# Comunicaciones.net
KiCad netlist of a schematic drawn in Altium Designer
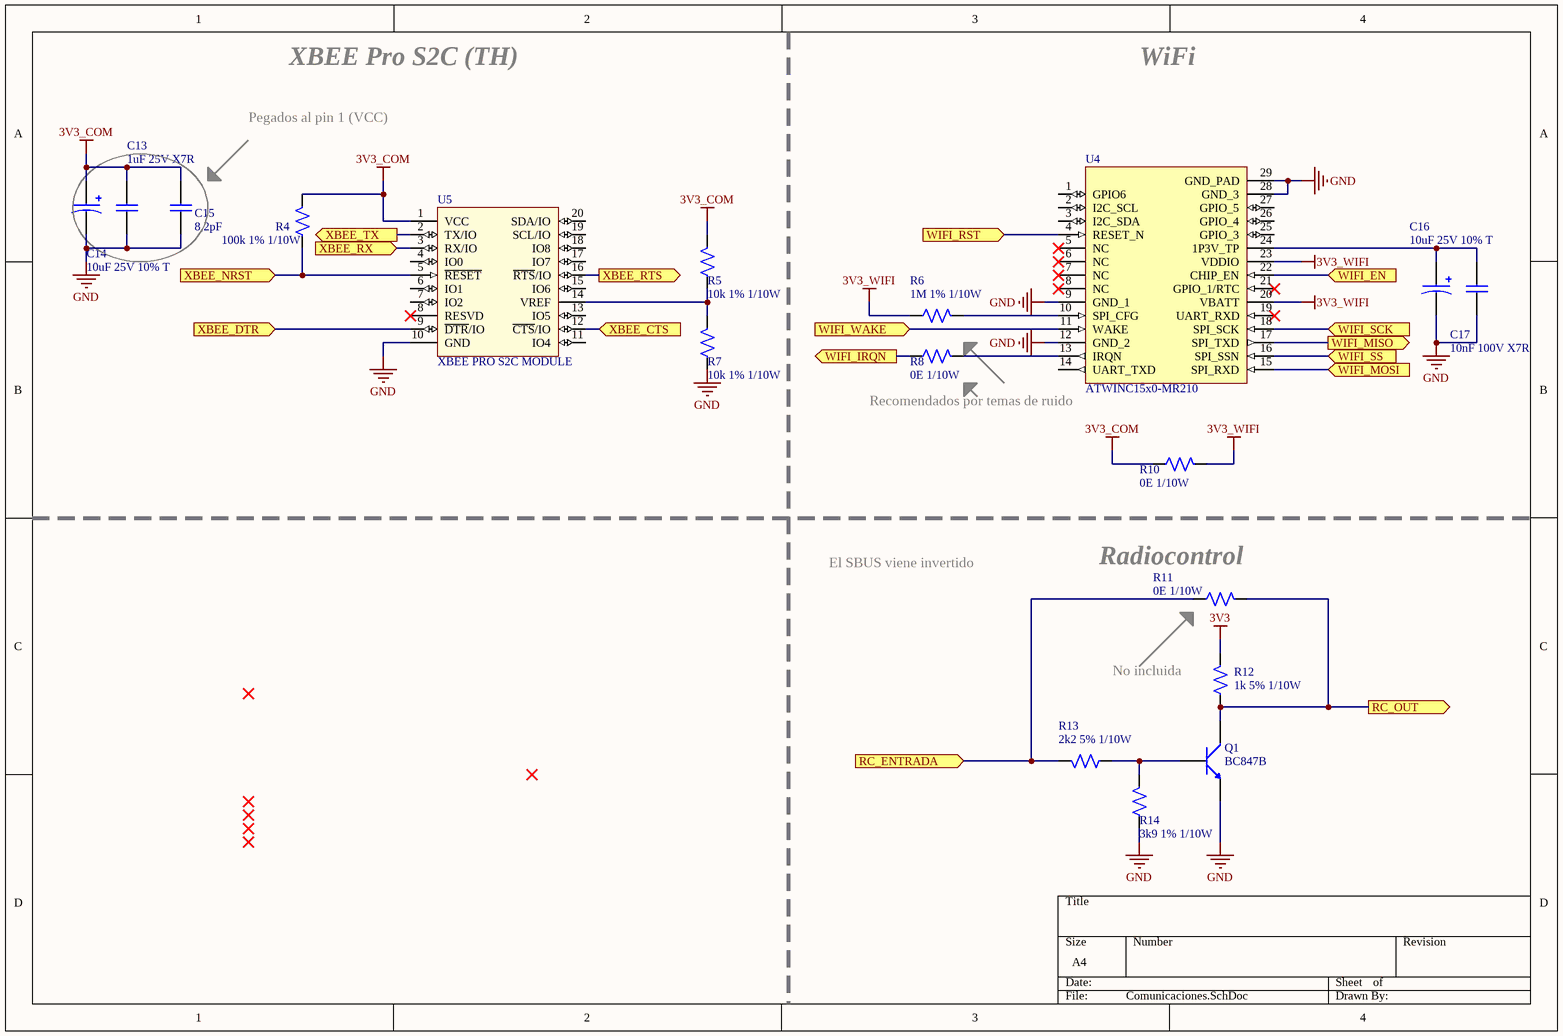
[diagram p0: Comunicaciones.SchDoc]

(export (version "E")
  (design (tool "Eeschema 10.0.6"))
  (components
    (comp (ref "C13")
      (value "1uF 25V X7R")
      (footprint "C0603")
      (description "Capacitor de placas paralelas")
      (libsource (lib "HW_Dron_V2") (part "Capacitor"))
    )
    (comp (ref "C14")
      (value "10uF 25V 10% T")
      (footprint "AVX_C")
      (description "Capacitor polarizado")
      (libsource (lib "HW_Dron_V2") (part "CapaPol"))
    )
    (comp (ref "C15")
      (value "8,2pF 50V COG 5%")
      (footprint "C0603")
      (description "Capacitor de placas paralelas")
      (fields (field (name "VALOR") "8,2pF"))
      (libsource (lib "HW_Dron_V2") (part "Capacitor"))
    )
    (comp (ref "C16")
      (value "10uF 25V 10% T")
      (footprint "AVX_C")
      (description "Capacitor polarizado")
      (libsource (lib "HW_Dron_V2") (part "CapaPol"))
    )
    (comp (ref "C17")
      (value "10nF 100V X7R")
      (footprint "C0603")
      (description "Capacitor de placas paralelas")
      (libsource (lib "HW_Dron_V2") (part "Capacitor"))
    )
    (comp (ref "Q1")
      (value "BC847B")
      (footprint "SOT23")
      (description "Transistor bipolar de juntura NPN")
      (libsource (lib "HW_Dron_V2") (part "NPN"))
    )
    (comp (ref "R4")
      (value "100k 1% 1/10W")
      (footprint "R0603")
      (description "Resistencia")
      (libsource (lib "HW_Dron_V2") (part "Resistor"))
    )
    (comp (ref "R5")
      (value "10k 1% 1/10W")
      (footprint "R0603")
      (description "Resistencia")
      (libsource (lib "HW_Dron_V2") (part "Resistor"))
    )
    (comp (ref "R6")
      (value "1M 1% 1/10W")
      (footprint "R0603")
      (description "Resistencia")
      (libsource (lib "HW_Dron_V2") (part "Resistor"))
    )
    (comp (ref "R7")
      (value "10k 1% 1/10W")
      (footprint "R0603")
      (description "Resistencia")
      (libsource (lib "HW_Dron_V2") (part "Resistor"))
    )
    (comp (ref "R8")
      (value "0E 1/10W")
      (footprint "R0603")
      (description "Resistencia")
      (libsource (lib "HW_Dron_V2") (part "Resistor"))
    )
    (comp (ref "R10")
      (value "0E 1/10W")
      (footprint "R0805")
      (description "Resistencia")
      (libsource (lib "HW_Dron_V2") (part "Resistor"))
    )
    (comp (ref "R11")
      (value "0E 1/10W")
      (footprint "R0603")
      (description "Resistencia")
      (libsource (lib "HW_Dron_V2") (part "Resistor"))
    )
    (comp (ref "R12")
      (value "1k 5% 1/10W")
      (footprint "R0603")
      (description "Resistencia")
      (libsource (lib "HW_Dron_V2") (part "Resistor"))
    )
    (comp (ref "R13")
      (value "2k2 5% 1/10W")
      (footprint "R0603")
      (description "Resistencia")
      (libsource (lib "HW_Dron_V2") (part "Resistor"))
    )
    (comp (ref "R14")
      (value "3k9 1% 1/10W")
      (footprint "R0603")
      (description "Resistencia")
      (libsource (lib "HW_Dron_V2") (part "Resistor"))
    )
    (comp (ref "U4")
      (value "ATWINC15x0-MR210")
      (footprint "ATWINC15x0-MR210PB")
      (description "IEEE 802.11 b/g/n SmartConnect  IoT Module")
      (libsource (lib "HW_Dron_V2") (part "ATWINC15x0-MR210"))
    )
    (comp (ref "U5")
      (value "XBEE PRO S2C MODULE")
      (footprint "XbeePRO")
      (description "Conector modulo Zigbee Series 2 C")
      (libsource (lib "HW_Dron_V2") (part "XbeePRO_S2C"))
    )
  )
  (nets
    (net (code "1") (name "/RC_ENTRADA") (class "Default")
      (node (ref "R11") (pin "1") (pinfunction "1_1") (pintype "passive"))
      (node (ref "R13") (pin "2") (pinfunction "2_2") (pintype "passive"))
    )
    (net (code "2") (name "/RC_OUT") (class "Default")
      (node (ref "Q1") (pin "2") (pinfunction "C_2") (pintype "passive"))
      (node (ref "R11") (pin "2") (pinfunction "2_2") (pintype "passive"))
      (node (ref "R12") (pin "1") (pinfunction "1_1") (pintype "passive"))
    )
    (net (code "3") (name "/WIFI_EN") (class "Default")
      (node (ref "U4") (pin "22") (pinfunction "CHIP_EN_22") (pintype "input"))
    )
    (net (code "4") (name "/WIFI_IRQN") (class "Default")
      (node (ref "R8") (pin "1") (pinfunction "1_1") (pintype "passive"))
    )
    (net (code "5") (name "/WIFI_MISO") (class "Default")
      (node (ref "U4") (pin "17") (pinfunction "SPI_TXD_17") (pintype "output"))
    )
    (net (code "6") (name "/WIFI_MOSI") (class "Default")
      (node (ref "U4") (pin "15") (pinfunction "SPI_RXD_15") (pintype "input"))
    )
    (net (code "7") (name "/WIFI_RST") (class "Default")
      (node (ref "U4") (pin "4") (pinfunction "RESET_N_4") (pintype "input"))
    )
    (net (code "8") (name "/WIFI_SCK") (class "Default")
      (node (ref "U4") (pin "18") (pinfunction "SPI_SCK_18") (pintype "input"))
    )
    (net (code "9") (name "/WIFI_SS") (class "Default")
      (node (ref "U4") (pin "16") (pinfunction "SPI_SSN_16") (pintype "input"))
    )
    (net (code "10") (name "/WIFI_WAKE") (class "Default")
      (node (ref "U4") (pin "11") (pinfunction "WAKE_11") (pintype "input"))
    )
    (net (code "11") (name "/XBEE_CTS") (class "Default")
      (node (ref "U5") (pin "12") (pinfunction "~{CTS}/IO_12") (pintype "bidirectional"))
    )
    (net (code "12") (name "/XBEE_DTR") (class "Default")
      (node (ref "U5") (pin "9") (pinfunction "~{DTR}/IO_9") (pintype "bidirectional"))
    )
    (net (code "13") (name "/XBEE_NRST") (class "Default")
      (node (ref "R4") (pin "1") (pinfunction "1_1") (pintype "passive"))
      (node (ref "U5") (pin "5") (pinfunction "~{RESET}_5") (pintype "input"))
    )
    (net (code "14") (name "/XBEE_RTS") (class "Default")
      (node (ref "U5") (pin "16") (pinfunction "~{RTS}/IO_16") (pintype "bidirectional"))
    )
    (net (code "15") (name "/XBEE_RX") (class "Default")
      (node (ref "U5") (pin "3") (pinfunction "RX/IO_3") (pintype "bidirectional"))
    )
    (net (code "16") (name "/XBEE_TX") (class "Default")
      (node (ref "U5") (pin "2") (pinfunction "TX/IO_2") (pintype "bidirectional"))
    )
    (net (code "17") (name "3V3") (class "Default")
      (node (ref "R12") (pin "2") (pinfunction "2_2") (pintype "passive"))
    )
    (net (code "18") (name "3V3_COM") (class "Default")
      (node (ref "C13") (pin "1") (pinfunction "1_1") (pintype "passive"))
      (node (ref "C14") (pin "1") (pinfunction "1_1") (pintype "passive"))
      (node (ref "C15") (pin "1") (pinfunction "1_1") (pintype "passive"))
      (node (ref "R10") (pin "1") (pinfunction "1_1") (pintype "passive"))
      (node (ref "R4") (pin "2") (pinfunction "2_2") (pintype "passive"))
      (node (ref "R5") (pin "2") (pinfunction "2_2") (pintype "passive"))
      (node (ref "U5") (pin "1") (pinfunction "VCC_1") (pintype "power_in"))
    )
    (net (code "19") (name "3V3_WIFI") (class "Default")
      (node (ref "R10") (pin "2") (pinfunction "2_2") (pintype "passive"))
      (node (ref "R6") (pin "1") (pinfunction "1_1") (pintype "passive"))
      (node (ref "U4") (pin "20") (pinfunction "VBATT_20") (pintype "power_in"))
      (node (ref "U4") (pin "23") (pinfunction "VDDIO_23") (pintype "power_in"))
    )
    (net (code "20") (name "GND") (class "Default")
      (node (ref "C13") (pin "2") (pinfunction "2_2") (pintype "passive"))
      (node (ref "C14") (pin "2") (pinfunction "2_2") (pintype "passive"))
      (node (ref "C15") (pin "2") (pinfunction "2_2") (pintype "passive"))
      (node (ref "C16") (pin "2") (pinfunction "2_2") (pintype "passive"))
      (node (ref "C17") (pin "2") (pinfunction "2_2") (pintype "passive"))
      (node (ref "Q1") (pin "3") (pinfunction "E_3") (pintype "passive"))
      (node (ref "R14") (pin "1") (pinfunction "1_1") (pintype "passive"))
      (node (ref "R7") (pin "1") (pinfunction "1_1") (pintype "passive"))
      (node (ref "U4") (pin "12") (pinfunction "GND_2_12") (pintype "power_in"))
      (node (ref "U4") (pin "28") (pinfunction "GND_3_28") (pintype "power_in"))
      (node (ref "U4") (pin "29") (pinfunction "GND_PAD_29") (pintype "power_in"))
      (node (ref "U4") (pin "9") (pinfunction "GND_1_9") (pintype "power_in"))
      (node (ref "U5") (pin "10") (pinfunction "GND_10") (pintype "power_in"))
    )
    (net (code "21") (name "Net-(Q1-B)") (class "Default")
      (node (ref "Q1") (pin "1") (pinfunction "B_1") (pintype "passive"))
      (node (ref "R13") (pin "1") (pinfunction "1_1") (pintype "passive"))
      (node (ref "R14") (pin "2") (pinfunction "2_2") (pintype "passive"))
    )
    (net (code "22") (name "Net-(U4-1P3V_TP)") (class "Default")
      (node (ref "C16") (pin "1") (pinfunction "1_1") (pintype "passive"))
      (node (ref "C17") (pin "1") (pinfunction "1_1") (pintype "passive"))
      (node (ref "U4") (pin "24") (pinfunction "1P3V_TP_24") (pintype "power_in"))
    )
    (net (code "23") (name "Net-(U4-IRQN)") (class "Default")
      (node (ref "R8") (pin "2") (pinfunction "2_2") (pintype "passive"))
      (node (ref "U4") (pin "13") (pinfunction "IRQN_13") (pintype "output"))
    )
    (net (code "24") (name "Net-(U4-SPI_CFG)") (class "Default")
      (node (ref "R6") (pin "2") (pinfunction "2_2") (pintype "passive"))
      (node (ref "U4") (pin "10") (pinfunction "SPI_CFG_10") (pintype "input"))
    )
    (net (code "25") (name "Net-(U5-VREF)") (class "Default")
      (node (ref "R5") (pin "1") (pinfunction "1_1") (pintype "passive"))
      (node (ref "R7") (pin "2") (pinfunction "2_2") (pintype "passive"))
      (node (ref "U5") (pin "14") (pinfunction "VREF_14") (pintype "power_in"))
    )
    (net (code "26") (name "unconnected-(U4-GPIO6-Pad1)") (class "Default")
      (node (ref "U4") (pin "1") (pinfunction "GPIO6_1") (pintype "bidirectional"))
    )
    (net (code "27") (name "unconnected-(U4-GPIO_1{slash}RTC-Pad21)") (class "Default")
      (node (ref "U4") (pin "21") (pinfunction "GPIO_1/RTC_21") (pintype "input+no_connect"))
    )
    (net (code "28") (name "unconnected-(U4-GPIO_3-Pad25)") (class "Default")
      (node (ref "U4") (pin "25") (pinfunction "GPIO_3_25") (pintype "bidirectional"))
    )
    (net (code "29") (name "unconnected-(U4-GPIO_4-Pad26)") (class "Default")
      (node (ref "U4") (pin "26") (pinfunction "GPIO_4_26") (pintype "bidirectional"))
    )
    (net (code "30") (name "unconnected-(U4-GPIO_5-Pad27)") (class "Default")
      (node (ref "U4") (pin "27") (pinfunction "GPIO_5_27") (pintype "bidirectional"))
    )
    (net (code "31") (name "unconnected-(U4-I2C_SCL-Pad2)") (class "Default")
      (node (ref "U4") (pin "2") (pinfunction "I2C_SCL_2") (pintype "bidirectional"))
    )
    (net (code "32") (name "unconnected-(U4-I2C_SDA-Pad3)") (class "Default")
      (node (ref "U4") (pin "3") (pinfunction "I2C_SDA_3") (pintype "bidirectional"))
    )
    (net (code "33") (name "unconnected-(U4-NC-Pad5)") (class "Default")
      (node (ref "U4") (pin "5") (pinfunction "NC_5") (pintype "tri_state+no_connect"))
    )
    (net (code "34") (name "unconnected-(U4-NC-Pad6)") (class "Default")
      (node (ref "U4") (pin "6") (pinfunction "NC_6") (pintype "tri_state+no_connect"))
    )
    (net (code "35") (name "unconnected-(U4-NC-Pad7)") (class "Default")
      (node (ref "U4") (pin "7") (pinfunction "NC_7") (pintype "tri_state+no_connect"))
    )
    (net (code "36") (name "unconnected-(U4-NC-Pad8)") (class "Default")
      (node (ref "U4") (pin "8") (pinfunction "NC_8") (pintype "tri_state+no_connect"))
    )
    (net (code "37") (name "unconnected-(U4-UART_RXD-Pad19)") (class "Default")
      (node (ref "U4") (pin "19") (pinfunction "UART_RXD_19") (pintype "input+no_connect"))
    )
    (net (code "38") (name "unconnected-(U4-UART_TXD-Pad14)") (class "Default")
      (node (ref "U4") (pin "14") (pinfunction "UART_TXD_14") (pintype "output"))
    )
    (net (code "39") (name "unconnected-(U5-IO0-Pad4)") (class "Default")
      (node (ref "U5") (pin "4") (pinfunction "IO0_4") (pintype "bidirectional"))
    )
    (net (code "40") (name "unconnected-(U5-IO1-Pad6)") (class "Default")
      (node (ref "U5") (pin "6") (pinfunction "IO1_6") (pintype "bidirectional"))
    )
    (net (code "41") (name "unconnected-(U5-IO2-Pad7)") (class "Default")
      (node (ref "U5") (pin "7") (pinfunction "IO2_7") (pintype "bidirectional"))
    )
    (net (code "42") (name "unconnected-(U5-IO4-Pad11)") (class "Default")
      (node (ref "U5") (pin "11") (pinfunction "IO4_11") (pintype "bidirectional"))
    )
    (net (code "43") (name "unconnected-(U5-IO5-Pad13)") (class "Default")
      (node (ref "U5") (pin "13") (pinfunction "IO5_13") (pintype "bidirectional"))
    )
    (net (code "44") (name "unconnected-(U5-IO6-Pad15)") (class "Default")
      (node (ref "U5") (pin "15") (pinfunction "IO6_15") (pintype "bidirectional"))
    )
    (net (code "45") (name "unconnected-(U5-IO7-Pad17)") (class "Default")
      (node (ref "U5") (pin "17") (pinfunction "IO7_17") (pintype "bidirectional"))
    )
    (net (code "46") (name "unconnected-(U5-IO8-Pad18)") (class "Default")
      (node (ref "U5") (pin "18") (pinfunction "IO8_18") (pintype "bidirectional"))
    )
    (net (code "47") (name "unconnected-(U5-RESVD-Pad8)") (class "Default")
      (node (ref "U5") (pin "8") (pinfunction "RESVD_8") (pintype "passive+no_connect"))
    )
    (net (code "48") (name "unconnected-(U5-SCL{slash}IO-Pad19)") (class "Default")
      (node (ref "U5") (pin "19") (pinfunction "SCL/IO_19") (pintype "bidirectional"))
    )
    (net (code "49") (name "unconnected-(U5-SDA{slash}IO-Pad20)") (class "Default")
      (node (ref "U5") (pin "20") (pinfunction "SDA/IO_20") (pintype "bidirectional"))
    )
  )
)
